# simm_adapter.net
KiCad netlist of a schematic drawn in EAGLE
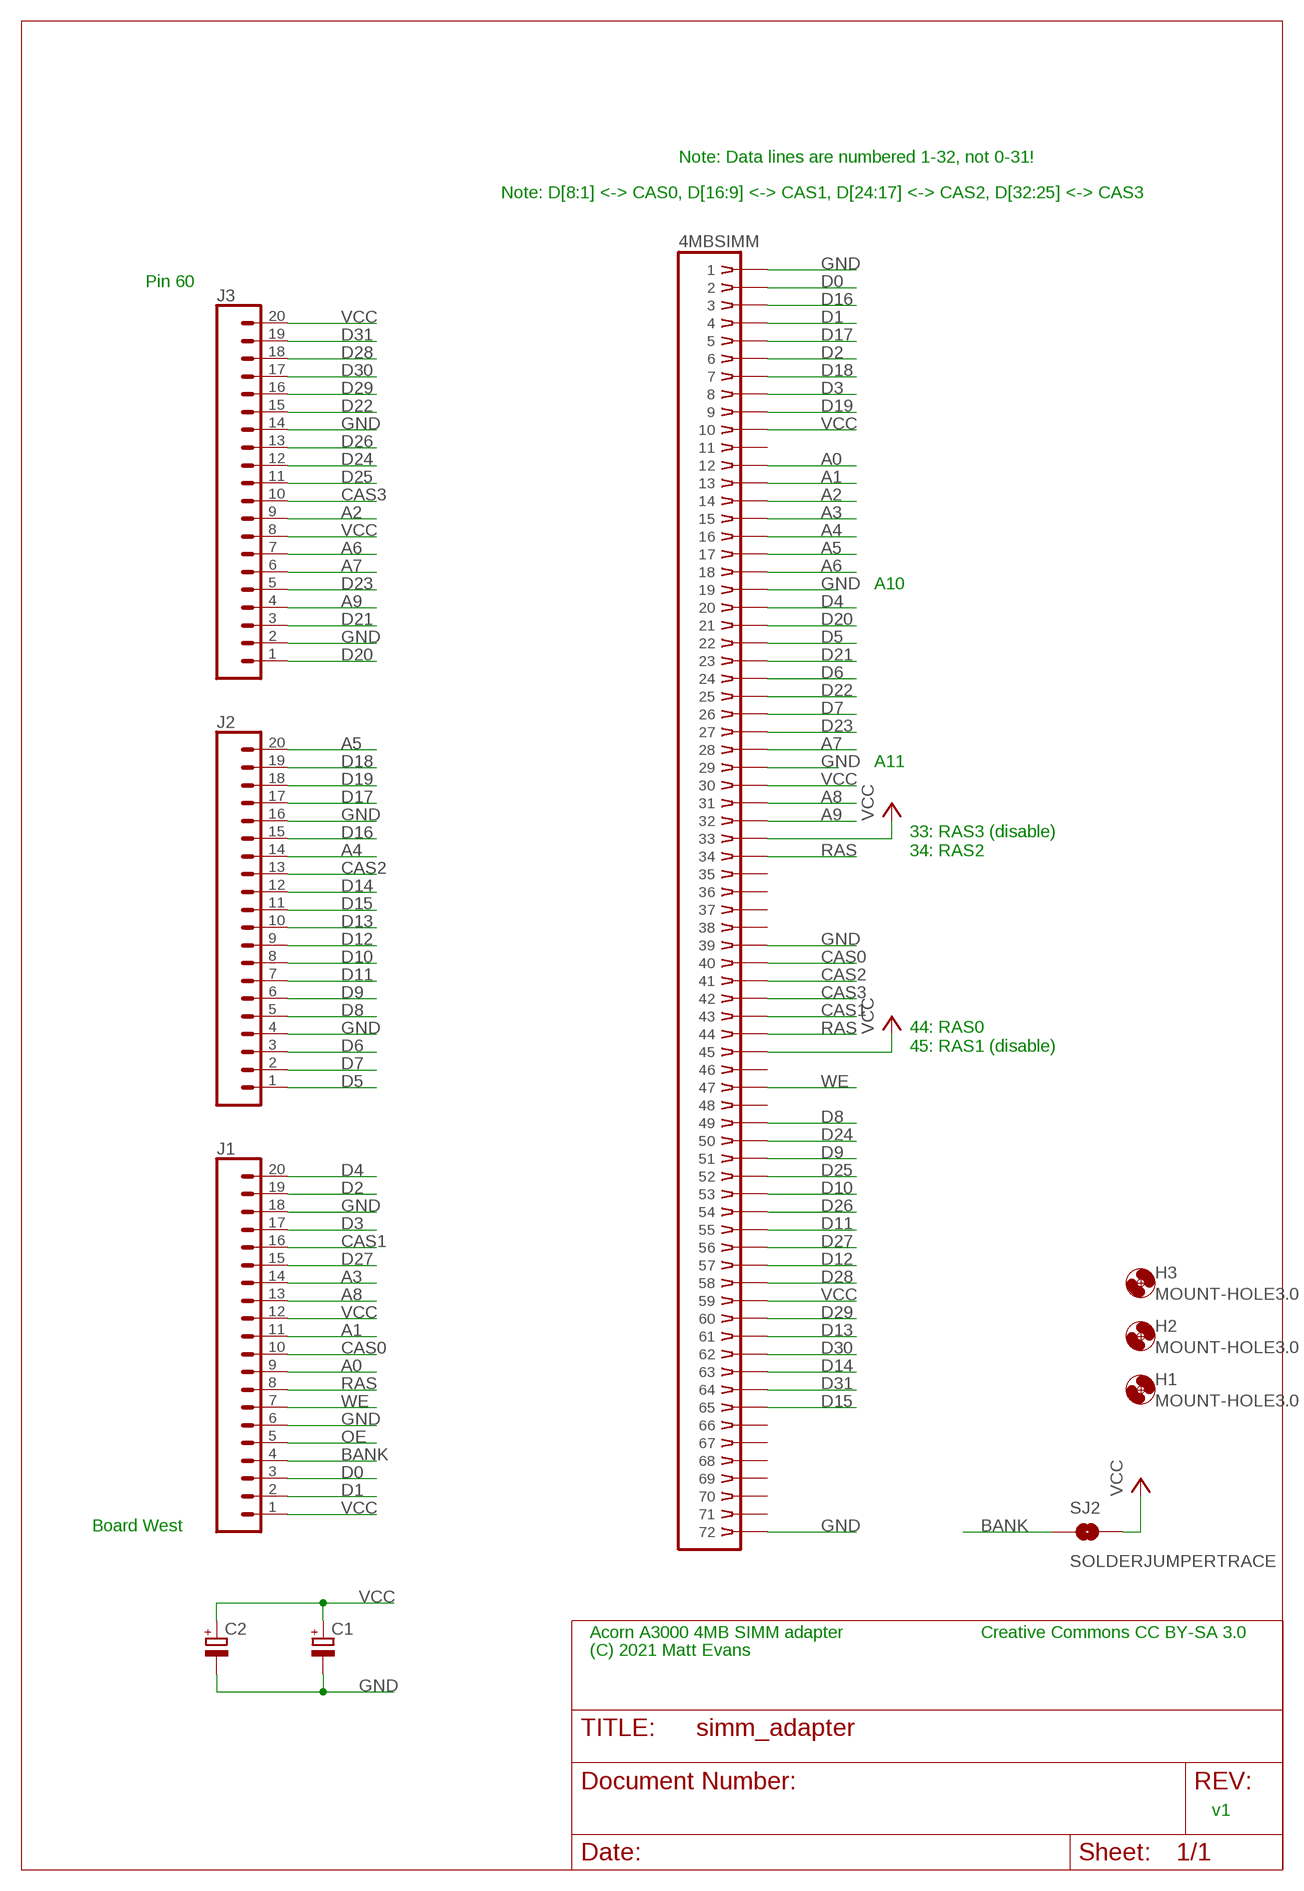
[diagram p0: schematic, sheet 1]

(export (version "E")
  (design (tool "Eeschema 10.0.6"))
  (components
    (comp (ref "4MBSIMM")
      (value "SIMM72")
      (footprint "eagle-import:73826962")
      (libsource (lib "eagle-import") (part "SIMM72"))
    )
    (comp (ref "C1")
      (value "CPOL-EUCT7343")
      (footprint "eagle-import:CT7343")
      (libsource (lib "eagle-import") (part "CPOL-EUCT7343"))
    )
    (comp (ref "C2")
      (value "CPOL-EUCT7343")
      (footprint "eagle-import:CT7343")
      (libsource (lib "eagle-import") (part "CPOL-EUCT7343"))
    )
    (comp (ref "H1")
      (value "MOUNT-HOLE3.0")
      (footprint "eagle-import:3,0")
      (libsource (lib "eagle-import") (part "MOUNT-HOLE3.0"))
    )
    (comp (ref "H2")
      (value "MOUNT-HOLE3.0")
      (footprint "eagle-import:3,0")
      (libsource (lib "eagle-import") (part "MOUNT-HOLE3.0"))
    )
    (comp (ref "H3")
      (value "MOUNT-HOLE3.0")
      (footprint "eagle-import:3,0")
      (libsource (lib "eagle-import") (part "MOUNT-HOLE3.0"))
    )
    (comp (ref "J1")
      (value "CONN_20")
      (footprint "eagle-import:1X20")
      (libsource (lib "eagle-import") (part "CONN_20"))
    )
    (comp (ref "J2")
      (value "CONN_20")
      (footprint "eagle-import:1X20")
      (libsource (lib "eagle-import") (part "CONN_20"))
    )
    (comp (ref "J3")
      (value "CONN_20")
      (footprint "eagle-import:1X20")
      (libsource (lib "eagle-import") (part "CONN_20"))
    )
    (comp (ref "SJ2")
      (value "SOLDERJUMPERTRACE")
      (footprint "eagle-import:SJ_2S-TRACE")
      (libsource (lib "eagle-import") (part "SOLDERJUMPERTRACE"))
    )
  )
  (nets
    (net (code "1") (name "/A0") (class "Default")
      (node (ref "4MBSIMM") (pin "12") (pinfunction "12_12") (pintype "passive"))
      (node (ref "J1") (pin "9") (pinfunction "9_9") (pintype "passive"))
    )
    (net (code "2") (name "/A1") (class "Default")
      (node (ref "4MBSIMM") (pin "13") (pinfunction "13_13") (pintype "passive"))
      (node (ref "J1") (pin "11") (pinfunction "11_11") (pintype "passive"))
    )
    (net (code "3") (name "/A2") (class "Default")
      (node (ref "4MBSIMM") (pin "14") (pinfunction "14_14") (pintype "passive"))
      (node (ref "J3") (pin "9") (pinfunction "9_9") (pintype "passive"))
    )
    (net (code "4") (name "/A3") (class "Default")
      (node (ref "4MBSIMM") (pin "15") (pinfunction "15_15") (pintype "passive"))
      (node (ref "J1") (pin "14") (pinfunction "14_14") (pintype "passive"))
    )
    (net (code "5") (name "/A4") (class "Default")
      (node (ref "4MBSIMM") (pin "16") (pinfunction "16_16") (pintype "passive"))
      (node (ref "J2") (pin "14") (pinfunction "14_14") (pintype "passive"))
    )
    (net (code "6") (name "/A5") (class "Default")
      (node (ref "4MBSIMM") (pin "17") (pinfunction "17_17") (pintype "passive"))
      (node (ref "J2") (pin "20") (pinfunction "20_20") (pintype "passive"))
    )
    (net (code "7") (name "/A6") (class "Default")
      (node (ref "4MBSIMM") (pin "18") (pinfunction "18_18") (pintype "passive"))
      (node (ref "J3") (pin "7") (pinfunction "7_7") (pintype "passive"))
    )
    (net (code "8") (name "/A7") (class "Default")
      (node (ref "4MBSIMM") (pin "28") (pinfunction "28_28") (pintype "passive"))
      (node (ref "J3") (pin "6") (pinfunction "6_6") (pintype "passive"))
    )
    (net (code "9") (name "/A8") (class "Default")
      (node (ref "4MBSIMM") (pin "31") (pinfunction "31_31") (pintype "passive"))
      (node (ref "J1") (pin "13") (pinfunction "13_13") (pintype "passive"))
    )
    (net (code "10") (name "/A9") (class "Default")
      (node (ref "4MBSIMM") (pin "32") (pinfunction "32_32") (pintype "passive"))
      (node (ref "J3") (pin "4") (pinfunction "4_4") (pintype "passive"))
    )
    (net (code "11") (name "/BANK") (class "Default")
      (node (ref "J1") (pin "4") (pinfunction "4_4") (pintype "passive"))
      (node (ref "SJ2") (pin "1") (pinfunction "1_1") (pintype "passive"))
    )
    (net (code "12") (name "/CAS0") (class "Default")
      (node (ref "4MBSIMM") (pin "40") (pinfunction "40_40") (pintype "passive"))
      (node (ref "J1") (pin "10") (pinfunction "10_10") (pintype "passive"))
    )
    (net (code "13") (name "/CAS1") (class "Default")
      (node (ref "4MBSIMM") (pin "43") (pinfunction "43_43") (pintype "passive"))
      (node (ref "J1") (pin "16") (pinfunction "16_16") (pintype "passive"))
    )
    (net (code "14") (name "/CAS2") (class "Default")
      (node (ref "4MBSIMM") (pin "41") (pinfunction "41_41") (pintype "passive"))
      (node (ref "J2") (pin "13") (pinfunction "13_13") (pintype "passive"))
    )
    (net (code "15") (name "/CAS3") (class "Default")
      (node (ref "4MBSIMM") (pin "42") (pinfunction "42_42") (pintype "passive"))
      (node (ref "J3") (pin "10") (pinfunction "10_10") (pintype "passive"))
    )
    (net (code "16") (name "/D0") (class "Default")
      (node (ref "4MBSIMM") (pin "2") (pinfunction "2_2") (pintype "passive"))
      (node (ref "J1") (pin "3") (pinfunction "3_3") (pintype "passive"))
    )
    (net (code "17") (name "/D1") (class "Default")
      (node (ref "4MBSIMM") (pin "4") (pinfunction "4_4") (pintype "passive"))
      (node (ref "J1") (pin "2") (pinfunction "2_2") (pintype "passive"))
    )
    (net (code "18") (name "/D2") (class "Default")
      (node (ref "4MBSIMM") (pin "6") (pinfunction "6_6") (pintype "passive"))
      (node (ref "J1") (pin "19") (pinfunction "19_19") (pintype "passive"))
    )
    (net (code "19") (name "/D3") (class "Default")
      (node (ref "4MBSIMM") (pin "8") (pinfunction "8_8") (pintype "passive"))
      (node (ref "J1") (pin "17") (pinfunction "17_17") (pintype "passive"))
    )
    (net (code "20") (name "/D4") (class "Default")
      (node (ref "4MBSIMM") (pin "20") (pinfunction "20_20") (pintype "passive"))
      (node (ref "J1") (pin "20") (pinfunction "20_20") (pintype "passive"))
    )
    (net (code "21") (name "/D5") (class "Default")
      (node (ref "4MBSIMM") (pin "22") (pinfunction "22_22") (pintype "passive"))
      (node (ref "J2") (pin "1") (pinfunction "1_1") (pintype "passive"))
    )
    (net (code "22") (name "/D6") (class "Default")
      (node (ref "4MBSIMM") (pin "24") (pinfunction "24_24") (pintype "passive"))
      (node (ref "J2") (pin "3") (pinfunction "3_3") (pintype "passive"))
    )
    (net (code "23") (name "/D7") (class "Default")
      (node (ref "4MBSIMM") (pin "26") (pinfunction "26_26") (pintype "passive"))
      (node (ref "J2") (pin "2") (pinfunction "2_2") (pintype "passive"))
    )
    (net (code "24") (name "/D8") (class "Default")
      (node (ref "4MBSIMM") (pin "49") (pinfunction "49_49") (pintype "passive"))
      (node (ref "J2") (pin "5") (pinfunction "5_5") (pintype "passive"))
    )
    (net (code "25") (name "/D9") (class "Default")
      (node (ref "4MBSIMM") (pin "51") (pinfunction "51_51") (pintype "passive"))
      (node (ref "J2") (pin "6") (pinfunction "6_6") (pintype "passive"))
    )
    (net (code "26") (name "/D10") (class "Default")
      (node (ref "4MBSIMM") (pin "53") (pinfunction "53_53") (pintype "passive"))
      (node (ref "J2") (pin "8") (pinfunction "8_8") (pintype "passive"))
    )
    (net (code "27") (name "/D11") (class "Default")
      (node (ref "4MBSIMM") (pin "55") (pinfunction "55_55") (pintype "passive"))
      (node (ref "J2") (pin "7") (pinfunction "7_7") (pintype "passive"))
    )
    (net (code "28") (name "/D12") (class "Default")
      (node (ref "4MBSIMM") (pin "57") (pinfunction "57_57") (pintype "passive"))
      (node (ref "J2") (pin "9") (pinfunction "9_9") (pintype "passive"))
    )
    (net (code "29") (name "/D13") (class "Default")
      (node (ref "4MBSIMM") (pin "61") (pinfunction "61_61") (pintype "passive"))
      (node (ref "J2") (pin "10") (pinfunction "10_10") (pintype "passive"))
    )
    (net (code "30") (name "/D14") (class "Default")
      (node (ref "4MBSIMM") (pin "63") (pinfunction "63_63") (pintype "passive"))
      (node (ref "J2") (pin "12") (pinfunction "12_12") (pintype "passive"))
    )
    (net (code "31") (name "/D15") (class "Default")
      (node (ref "4MBSIMM") (pin "65") (pinfunction "65_65") (pintype "passive"))
      (node (ref "J2") (pin "11") (pinfunction "11_11") (pintype "passive"))
    )
    (net (code "32") (name "/D16") (class "Default")
      (node (ref "4MBSIMM") (pin "3") (pinfunction "3_3") (pintype "passive"))
      (node (ref "J2") (pin "15") (pinfunction "15_15") (pintype "passive"))
    )
    (net (code "33") (name "/D17") (class "Default")
      (node (ref "4MBSIMM") (pin "5") (pinfunction "5_5") (pintype "passive"))
      (node (ref "J2") (pin "17") (pinfunction "17_17") (pintype "passive"))
    )
    (net (code "34") (name "/D18") (class "Default")
      (node (ref "4MBSIMM") (pin "7") (pinfunction "7_7") (pintype "passive"))
      (node (ref "J2") (pin "19") (pinfunction "19_19") (pintype "passive"))
    )
    (net (code "35") (name "/D19") (class "Default")
      (node (ref "4MBSIMM") (pin "9") (pinfunction "9_9") (pintype "passive"))
      (node (ref "J2") (pin "18") (pinfunction "18_18") (pintype "passive"))
    )
    (net (code "36") (name "/D20") (class "Default")
      (node (ref "4MBSIMM") (pin "21") (pinfunction "21_21") (pintype "passive"))
      (node (ref "J3") (pin "1") (pinfunction "1_1") (pintype "passive"))
    )
    (net (code "37") (name "/D21") (class "Default")
      (node (ref "4MBSIMM") (pin "23") (pinfunction "23_23") (pintype "passive"))
      (node (ref "J3") (pin "3") (pinfunction "3_3") (pintype "passive"))
    )
    (net (code "38") (name "/D22") (class "Default")
      (node (ref "4MBSIMM") (pin "25") (pinfunction "25_25") (pintype "passive"))
      (node (ref "J3") (pin "15") (pinfunction "15_15") (pintype "passive"))
    )
    (net (code "39") (name "/D23") (class "Default")
      (node (ref "4MBSIMM") (pin "27") (pinfunction "27_27") (pintype "passive"))
      (node (ref "J3") (pin "5") (pinfunction "5_5") (pintype "passive"))
    )
    (net (code "40") (name "/D24") (class "Default")
      (node (ref "4MBSIMM") (pin "50") (pinfunction "50_50") (pintype "passive"))
      (node (ref "J3") (pin "12") (pinfunction "12_12") (pintype "passive"))
    )
    (net (code "41") (name "/D25") (class "Default")
      (node (ref "4MBSIMM") (pin "52") (pinfunction "52_52") (pintype "passive"))
      (node (ref "J3") (pin "11") (pinfunction "11_11") (pintype "passive"))
    )
    (net (code "42") (name "/D26") (class "Default")
      (node (ref "4MBSIMM") (pin "54") (pinfunction "54_54") (pintype "passive"))
      (node (ref "J3") (pin "13") (pinfunction "13_13") (pintype "passive"))
    )
    (net (code "43") (name "/D27") (class "Default")
      (node (ref "4MBSIMM") (pin "56") (pinfunction "56_56") (pintype "passive"))
      (node (ref "J1") (pin "15") (pinfunction "15_15") (pintype "passive"))
    )
    (net (code "44") (name "/D28") (class "Default")
      (node (ref "4MBSIMM") (pin "58") (pinfunction "58_58") (pintype "passive"))
      (node (ref "J3") (pin "18") (pinfunction "18_18") (pintype "passive"))
    )
    (net (code "45") (name "/D29") (class "Default")
      (node (ref "4MBSIMM") (pin "60") (pinfunction "60_60") (pintype "passive"))
      (node (ref "J3") (pin "16") (pinfunction "16_16") (pintype "passive"))
    )
    (net (code "46") (name "/D30") (class "Default")
      (node (ref "4MBSIMM") (pin "62") (pinfunction "62_62") (pintype "passive"))
      (node (ref "J3") (pin "17") (pinfunction "17_17") (pintype "passive"))
    )
    (net (code "47") (name "/D31") (class "Default")
      (node (ref "4MBSIMM") (pin "64") (pinfunction "64_64") (pintype "passive"))
      (node (ref "J3") (pin "19") (pinfunction "19_19") (pintype "passive"))
    )
    (net (code "48") (name "/GND") (class "Default")
      (node (ref "4MBSIMM") (pin "1") (pinfunction "1_1") (pintype "passive"))
      (node (ref "4MBSIMM") (pin "19") (pinfunction "19_19") (pintype "passive"))
      (node (ref "4MBSIMM") (pin "29") (pinfunction "29_29") (pintype "passive"))
      (node (ref "4MBSIMM") (pin "39") (pinfunction "39_39") (pintype "passive"))
      (node (ref "4MBSIMM") (pin "72") (pinfunction "72_72") (pintype "passive"))
      (node (ref "C1") (pin "-") (pinfunction "-_-") (pintype "passive"))
      (node (ref "C2") (pin "-") (pinfunction "-_-") (pintype "passive"))
      (node (ref "J1") (pin "18") (pinfunction "18_18") (pintype "passive"))
      (node (ref "J1") (pin "6") (pinfunction "6_6") (pintype "passive"))
      (node (ref "J2") (pin "16") (pinfunction "16_16") (pintype "passive"))
      (node (ref "J2") (pin "4") (pinfunction "4_4") (pintype "passive"))
      (node (ref "J3") (pin "14") (pinfunction "14_14") (pintype "passive"))
      (node (ref "J3") (pin "2") (pinfunction "2_2") (pintype "passive"))
    )
    (net (code "49") (name "/OE") (class "Default")
      (node (ref "J1") (pin "5") (pinfunction "5_5") (pintype "passive"))
    )
    (net (code "50") (name "/RAS") (class "Default")
      (node (ref "4MBSIMM") (pin "34") (pinfunction "34_34") (pintype "passive"))
      (node (ref "4MBSIMM") (pin "44") (pinfunction "44_44") (pintype "passive"))
      (node (ref "J1") (pin "8") (pinfunction "8_8") (pintype "passive"))
    )
    (net (code "51") (name "/WE") (class "Default")
      (node (ref "4MBSIMM") (pin "47") (pinfunction "47_47") (pintype "passive"))
      (node (ref "J1") (pin "7") (pinfunction "7_7") (pintype "passive"))
    )
    (net (code "52") (name "VCC") (class "Default")
      (node (ref "4MBSIMM") (pin "10") (pinfunction "10_10") (pintype "passive"))
      (node (ref "4MBSIMM") (pin "30") (pinfunction "30_30") (pintype "passive"))
      (node (ref "4MBSIMM") (pin "33") (pinfunction "33_33") (pintype "passive"))
      (node (ref "4MBSIMM") (pin "45") (pinfunction "45_45") (pintype "passive"))
      (node (ref "4MBSIMM") (pin "59") (pinfunction "59_59") (pintype "passive"))
      (node (ref "C1") (pin "+") (pinfunction "+_+") (pintype "passive"))
      (node (ref "C2") (pin "+") (pinfunction "+_+") (pintype "passive"))
      (node (ref "J1") (pin "1") (pinfunction "1_1") (pintype "passive"))
      (node (ref "J1") (pin "12") (pinfunction "12_12") (pintype "passive"))
      (node (ref "J3") (pin "20") (pinfunction "20_20") (pintype "passive"))
      (node (ref "J3") (pin "8") (pinfunction "8_8") (pintype "passive"))
      (node (ref "SJ2") (pin "2") (pinfunction "2_2") (pintype "passive"))
    )
    (net (code "53") (name "unconnected-(4MBSIMM-Pad11)") (class "Default")
      (node (ref "4MBSIMM") (pin "11") (pinfunction "11_11") (pintype "passive"))
    )
    (net (code "54") (name "unconnected-(4MBSIMM-Pad35)") (class "Default")
      (node (ref "4MBSIMM") (pin "35") (pinfunction "35_35") (pintype "passive"))
    )
    (net (code "55") (name "unconnected-(4MBSIMM-Pad36)") (class "Default")
      (node (ref "4MBSIMM") (pin "36") (pinfunction "36_36") (pintype "passive"))
    )
    (net (code "56") (name "unconnected-(4MBSIMM-Pad37)") (class "Default")
      (node (ref "4MBSIMM") (pin "37") (pinfunction "37_37") (pintype "passive"))
    )
    (net (code "57") (name "unconnected-(4MBSIMM-Pad38)") (class "Default")
      (node (ref "4MBSIMM") (pin "38") (pinfunction "38_38") (pintype "passive"))
    )
    (net (code "58") (name "unconnected-(4MBSIMM-Pad46)") (class "Default")
      (node (ref "4MBSIMM") (pin "46") (pinfunction "46_46") (pintype "passive"))
    )
    (net (code "59") (name "unconnected-(4MBSIMM-Pad48)") (class "Default")
      (node (ref "4MBSIMM") (pin "48") (pinfunction "48_48") (pintype "passive"))
    )
    (net (code "60") (name "unconnected-(4MBSIMM-Pad66)") (class "Default")
      (node (ref "4MBSIMM") (pin "66") (pinfunction "66_66") (pintype "passive"))
    )
    (net (code "61") (name "unconnected-(4MBSIMM-Pad67)") (class "Default")
      (node (ref "4MBSIMM") (pin "67") (pinfunction "67_67") (pintype "passive"))
    )
    (net (code "62") (name "unconnected-(4MBSIMM-Pad68)") (class "Default")
      (node (ref "4MBSIMM") (pin "68") (pinfunction "68_68") (pintype "passive"))
    )
    (net (code "63") (name "unconnected-(4MBSIMM-Pad69)") (class "Default")
      (node (ref "4MBSIMM") (pin "69") (pinfunction "69_69") (pintype "passive"))
    )
    (net (code "64") (name "unconnected-(4MBSIMM-Pad70)") (class "Default")
      (node (ref "4MBSIMM") (pin "70") (pinfunction "70_70") (pintype "passive"))
    )
    (net (code "65") (name "unconnected-(4MBSIMM-Pad71)") (class "Default")
      (node (ref "4MBSIMM") (pin "71") (pinfunction "71_71") (pintype "passive"))
    )
  )
)
